# IO.net
KiCad netlist of a schematic drawn in Altium Designer
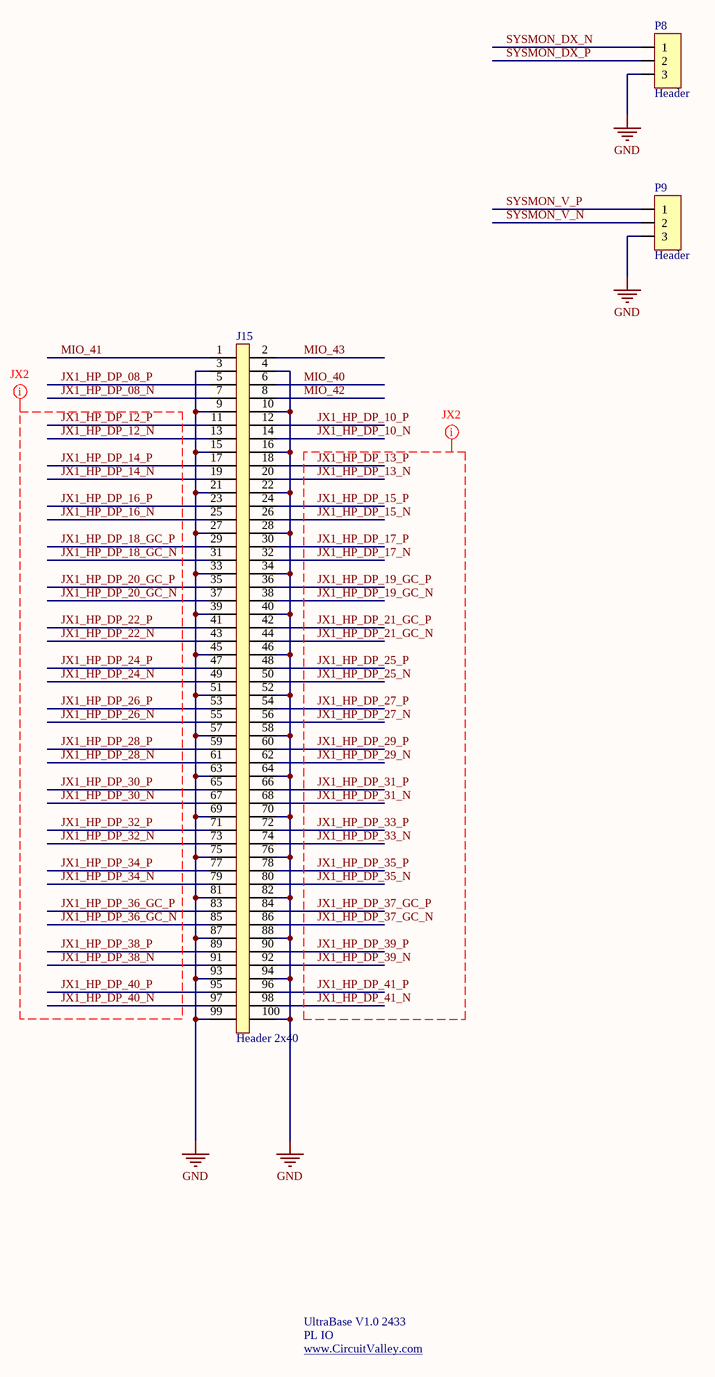
[diagram p0: IO.SchDoc]

(export (version "E")
  (design (tool "Eeschema 10.0.6"))
  (components
    (comp (ref "J15")
      (value "Header 2x40")
      (footprint "Header_2x50")
      (libsource (lib "cvlib") (part "Header_2x50"))
    )
    (comp (ref "P8")
      (value "Header")
      (footprint "Header3x")
      (description "3 Pin Header")
      (libsource (lib "cvlib") (part "Header_3Pin"))
    )
    (comp (ref "P9")
      (value "Header")
      (footprint "Header3x")
      (description "3 Pin Header")
      (libsource (lib "cvlib") (part "Header_3Pin"))
    )
  )
  (nets
    (net (code "1") (name "/JX1_HP_DP_08_N") (class "Default")
      (node (ref "J15") (pin "7") (pinfunction "7_7") (pintype "passive"))
    )
    (net (code "2") (name "/JX1_HP_DP_08_P") (class "Default")
      (node (ref "J15") (pin "5") (pinfunction "5_5") (pintype "passive"))
    )
    (net (code "3") (name "/JX1_HP_DP_10_N") (class "Default")
      (node (ref "J15") (pin "14") (pinfunction "14_14") (pintype "passive"))
    )
    (net (code "4") (name "/JX1_HP_DP_10_P") (class "Default")
      (node (ref "J15") (pin "12") (pinfunction "12_12") (pintype "passive"))
    )
    (net (code "5") (name "/JX1_HP_DP_12_N") (class "Default")
      (node (ref "J15") (pin "13") (pinfunction "13_13") (pintype "passive"))
    )
    (net (code "6") (name "/JX1_HP_DP_12_P") (class "Default")
      (node (ref "J15") (pin "11") (pinfunction "11_11") (pintype "passive"))
    )
    (net (code "7") (name "/JX1_HP_DP_13_N") (class "Default")
      (node (ref "J15") (pin "20") (pinfunction "20_20") (pintype "passive"))
    )
    (net (code "8") (name "/JX1_HP_DP_13_P") (class "Default")
      (node (ref "J15") (pin "18") (pinfunction "18_18") (pintype "passive"))
    )
    (net (code "9") (name "/JX1_HP_DP_14_N") (class "Default")
      (node (ref "J15") (pin "19") (pinfunction "19_19") (pintype "passive"))
    )
    (net (code "10") (name "/JX1_HP_DP_14_P") (class "Default")
      (node (ref "J15") (pin "17") (pinfunction "17_17") (pintype "passive"))
    )
    (net (code "11") (name "/JX1_HP_DP_15_N") (class "Default")
      (node (ref "J15") (pin "26") (pinfunction "26_26") (pintype "passive"))
    )
    (net (code "12") (name "/JX1_HP_DP_15_P") (class "Default")
      (node (ref "J15") (pin "24") (pinfunction "24_24") (pintype "passive"))
    )
    (net (code "13") (name "/JX1_HP_DP_16_N") (class "Default")
      (node (ref "J15") (pin "25") (pinfunction "25_25") (pintype "passive"))
    )
    (net (code "14") (name "/JX1_HP_DP_16_P") (class "Default")
      (node (ref "J15") (pin "23") (pinfunction "23_23") (pintype "passive"))
    )
    (net (code "15") (name "/JX1_HP_DP_17_N") (class "Default")
      (node (ref "J15") (pin "32") (pinfunction "32_32") (pintype "passive"))
    )
    (net (code "16") (name "/JX1_HP_DP_17_P") (class "Default")
      (node (ref "J15") (pin "30") (pinfunction "30_30") (pintype "passive"))
    )
    (net (code "17") (name "/JX1_HP_DP_18_GC_N") (class "Default")
      (node (ref "J15") (pin "31") (pinfunction "31_31") (pintype "passive"))
    )
    (net (code "18") (name "/JX1_HP_DP_18_GC_P") (class "Default")
      (node (ref "J15") (pin "29") (pinfunction "29_29") (pintype "passive"))
    )
    (net (code "19") (name "/JX1_HP_DP_19_GC_N") (class "Default")
      (node (ref "J15") (pin "38") (pinfunction "38_38") (pintype "passive"))
    )
    (net (code "20") (name "/JX1_HP_DP_19_GC_P") (class "Default")
      (node (ref "J15") (pin "36") (pinfunction "36_36") (pintype "passive"))
    )
    (net (code "21") (name "/JX1_HP_DP_20_GC_N") (class "Default")
      (node (ref "J15") (pin "37") (pinfunction "37_37") (pintype "passive"))
    )
    (net (code "22") (name "/JX1_HP_DP_20_GC_P") (class "Default")
      (node (ref "J15") (pin "35") (pinfunction "35_35") (pintype "passive"))
    )
    (net (code "23") (name "/JX1_HP_DP_21_GC_N") (class "Default")
      (node (ref "J15") (pin "44") (pinfunction "44_44") (pintype "passive"))
    )
    (net (code "24") (name "/JX1_HP_DP_21_GC_P") (class "Default")
      (node (ref "J15") (pin "42") (pinfunction "42_42") (pintype "passive"))
    )
    (net (code "25") (name "/JX1_HP_DP_22_N") (class "Default")
      (node (ref "J15") (pin "43") (pinfunction "43_43") (pintype "passive"))
    )
    (net (code "26") (name "/JX1_HP_DP_22_P") (class "Default")
      (node (ref "J15") (pin "41") (pinfunction "41_41") (pintype "passive"))
    )
    (net (code "27") (name "/JX1_HP_DP_24_N") (class "Default")
      (node (ref "J15") (pin "49") (pinfunction "49_49") (pintype "passive"))
    )
    (net (code "28") (name "/JX1_HP_DP_24_P") (class "Default")
      (node (ref "J15") (pin "47") (pinfunction "47_47") (pintype "passive"))
    )
    (net (code "29") (name "/JX1_HP_DP_25_N") (class "Default")
      (node (ref "J15") (pin "50") (pinfunction "50_50") (pintype "passive"))
    )
    (net (code "30") (name "/JX1_HP_DP_25_P") (class "Default")
      (node (ref "J15") (pin "48") (pinfunction "48_48") (pintype "passive"))
    )
    (net (code "31") (name "/JX1_HP_DP_26_N") (class "Default")
      (node (ref "J15") (pin "55") (pinfunction "55_55") (pintype "passive"))
    )
    (net (code "32") (name "/JX1_HP_DP_26_P") (class "Default")
      (node (ref "J15") (pin "53") (pinfunction "53_53") (pintype "passive"))
    )
    (net (code "33") (name "/JX1_HP_DP_27_N") (class "Default")
      (node (ref "J15") (pin "56") (pinfunction "56_56") (pintype "passive"))
    )
    (net (code "34") (name "/JX1_HP_DP_27_P") (class "Default")
      (node (ref "J15") (pin "54") (pinfunction "54_54") (pintype "passive"))
    )
    (net (code "35") (name "/JX1_HP_DP_28_N") (class "Default")
      (node (ref "J15") (pin "61") (pinfunction "61_61") (pintype "passive"))
    )
    (net (code "36") (name "/JX1_HP_DP_28_P") (class "Default")
      (node (ref "J15") (pin "59") (pinfunction "59_59") (pintype "passive"))
    )
    (net (code "37") (name "/JX1_HP_DP_29_N") (class "Default")
      (node (ref "J15") (pin "62") (pinfunction "62_62") (pintype "passive"))
    )
    (net (code "38") (name "/JX1_HP_DP_29_P") (class "Default")
      (node (ref "J15") (pin "60") (pinfunction "60_60") (pintype "passive"))
    )
    (net (code "39") (name "/JX1_HP_DP_30_N") (class "Default")
      (node (ref "J15") (pin "67") (pinfunction "67_67") (pintype "passive"))
    )
    (net (code "40") (name "/JX1_HP_DP_30_P") (class "Default")
      (node (ref "J15") (pin "65") (pinfunction "65_65") (pintype "passive"))
    )
    (net (code "41") (name "/JX1_HP_DP_31_N") (class "Default")
      (node (ref "J15") (pin "68") (pinfunction "68_68") (pintype "passive"))
    )
    (net (code "42") (name "/JX1_HP_DP_31_P") (class "Default")
      (node (ref "J15") (pin "66") (pinfunction "66_66") (pintype "passive"))
    )
    (net (code "43") (name "/JX1_HP_DP_32_N") (class "Default")
      (node (ref "J15") (pin "73") (pinfunction "73_73") (pintype "passive"))
    )
    (net (code "44") (name "/JX1_HP_DP_32_P") (class "Default")
      (node (ref "J15") (pin "71") (pinfunction "71_71") (pintype "passive"))
    )
    (net (code "45") (name "/JX1_HP_DP_33_N") (class "Default")
      (node (ref "J15") (pin "74") (pinfunction "74_74") (pintype "passive"))
    )
    (net (code "46") (name "/JX1_HP_DP_33_P") (class "Default")
      (node (ref "J15") (pin "72") (pinfunction "72_72") (pintype "passive"))
    )
    (net (code "47") (name "/JX1_HP_DP_34_N") (class "Default")
      (node (ref "J15") (pin "79") (pinfunction "79_79") (pintype "passive"))
    )
    (net (code "48") (name "/JX1_HP_DP_34_P") (class "Default")
      (node (ref "J15") (pin "77") (pinfunction "77_77") (pintype "passive"))
    )
    (net (code "49") (name "/JX1_HP_DP_35_N") (class "Default")
      (node (ref "J15") (pin "80") (pinfunction "80_80") (pintype "passive"))
    )
    (net (code "50") (name "/JX1_HP_DP_35_P") (class "Default")
      (node (ref "J15") (pin "78") (pinfunction "78_78") (pintype "passive"))
    )
    (net (code "51") (name "/JX1_HP_DP_36_GC_N") (class "Default")
      (node (ref "J15") (pin "85") (pinfunction "85_85") (pintype "passive"))
    )
    (net (code "52") (name "/JX1_HP_DP_36_GC_P") (class "Default")
      (node (ref "J15") (pin "83") (pinfunction "83_83") (pintype "passive"))
    )
    (net (code "53") (name "/JX1_HP_DP_37_GC_N") (class "Default")
      (node (ref "J15") (pin "86") (pinfunction "86_86") (pintype "passive"))
    )
    (net (code "54") (name "/JX1_HP_DP_37_GC_P") (class "Default")
      (node (ref "J15") (pin "84") (pinfunction "84_84") (pintype "passive"))
    )
    (net (code "55") (name "/JX1_HP_DP_38_N") (class "Default")
      (node (ref "J15") (pin "91") (pinfunction "91_91") (pintype "passive"))
    )
    (net (code "56") (name "/JX1_HP_DP_38_P") (class "Default")
      (node (ref "J15") (pin "89") (pinfunction "89_89") (pintype "passive"))
    )
    (net (code "57") (name "/JX1_HP_DP_39_N") (class "Default")
      (node (ref "J15") (pin "92") (pinfunction "92_92") (pintype "passive"))
    )
    (net (code "58") (name "/JX1_HP_DP_39_P") (class "Default")
      (node (ref "J15") (pin "90") (pinfunction "90_90") (pintype "passive"))
    )
    (net (code "59") (name "/JX1_HP_DP_40_N") (class "Default")
      (node (ref "J15") (pin "97") (pinfunction "97_97") (pintype "passive"))
    )
    (net (code "60") (name "/JX1_HP_DP_40_P") (class "Default")
      (node (ref "J15") (pin "95") (pinfunction "95_95") (pintype "passive"))
    )
    (net (code "61") (name "/JX1_HP_DP_41_N") (class "Default")
      (node (ref "J15") (pin "98") (pinfunction "98_98") (pintype "passive"))
    )
    (net (code "62") (name "/JX1_HP_DP_41_P") (class "Default")
      (node (ref "J15") (pin "96") (pinfunction "96_96") (pintype "passive"))
    )
    (net (code "63") (name "/MIO_40") (class "Default")
      (node (ref "J15") (pin "6") (pinfunction "6_6") (pintype "passive"))
    )
    (net (code "64") (name "/MIO_41") (class "Default")
      (node (ref "J15") (pin "1") (pinfunction "1_1") (pintype "passive"))
    )
    (net (code "65") (name "/MIO_42") (class "Default")
      (node (ref "J15") (pin "8") (pinfunction "8_8") (pintype "passive"))
    )
    (net (code "66") (name "/MIO_43") (class "Default")
      (node (ref "J15") (pin "2") (pinfunction "2_2") (pintype "passive"))
    )
    (net (code "67") (name "/SYSMON_DX_N") (class "Default")
      (node (ref "P8") (pin "1") (pinfunction "1_1") (pintype "passive"))
    )
    (net (code "68") (name "/SYSMON_DX_P") (class "Default")
      (node (ref "P8") (pin "2") (pinfunction "2_2") (pintype "passive"))
    )
    (net (code "69") (name "/SYSMON_V_N") (class "Default")
      (node (ref "P9") (pin "2") (pinfunction "2_2") (pintype "passive"))
    )
    (net (code "70") (name "/SYSMON_V_P") (class "Default")
      (node (ref "P9") (pin "1") (pinfunction "1_1") (pintype "passive"))
    )
    (net (code "71") (name "GND") (class "Default")
      (node (ref "J15") (pin "10") (pinfunction "10_10") (pintype "passive"))
      (node (ref "J15") (pin "100") (pinfunction "100_100") (pintype "passive"))
      (node (ref "J15") (pin "15") (pinfunction "15_15") (pintype "passive"))
      (node (ref "J15") (pin "16") (pinfunction "16_16") (pintype "passive"))
      (node (ref "J15") (pin "21") (pinfunction "21_21") (pintype "passive"))
      (node (ref "J15") (pin "22") (pinfunction "22_22") (pintype "passive"))
      (node (ref "J15") (pin "27") (pinfunction "27_27") (pintype "passive"))
      (node (ref "J15") (pin "28") (pinfunction "28_28") (pintype "passive"))
      (node (ref "J15") (pin "3") (pinfunction "3_3") (pintype "passive"))
      (node (ref "J15") (pin "33") (pinfunction "33_33") (pintype "passive"))
      (node (ref "J15") (pin "34") (pinfunction "34_34") (pintype "passive"))
      (node (ref "J15") (pin "39") (pinfunction "39_39") (pintype "passive"))
      (node (ref "J15") (pin "4") (pinfunction "4_4") (pintype "passive"))
      (node (ref "J15") (pin "40") (pinfunction "40_40") (pintype "passive"))
      (node (ref "J15") (pin "45") (pinfunction "45_45") (pintype "passive"))
      (node (ref "J15") (pin "46") (pinfunction "46_46") (pintype "passive"))
      (node (ref "J15") (pin "51") (pinfunction "51_51") (pintype "passive"))
      (node (ref "J15") (pin "52") (pinfunction "52_52") (pintype "passive"))
      (node (ref "J15") (pin "57") (pinfunction "57_57") (pintype "passive"))
      (node (ref "J15") (pin "58") (pinfunction "58_58") (pintype "passive"))
      (node (ref "J15") (pin "63") (pinfunction "63_63") (pintype "passive"))
      (node (ref "J15") (pin "64") (pinfunction "64_64") (pintype "passive"))
      (node (ref "J15") (pin "69") (pinfunction "69_69") (pintype "passive"))
      (node (ref "J15") (pin "70") (pinfunction "70_70") (pintype "passive"))
      (node (ref "J15") (pin "75") (pinfunction "75_75") (pintype "passive"))
      (node (ref "J15") (pin "76") (pinfunction "76_76") (pintype "passive"))
      (node (ref "J15") (pin "81") (pinfunction "81_81") (pintype "passive"))
      (node (ref "J15") (pin "82") (pinfunction "82_82") (pintype "passive"))
      (node (ref "J15") (pin "87") (pinfunction "87_87") (pintype "passive"))
      (node (ref "J15") (pin "88") (pinfunction "88_88") (pintype "passive"))
      (node (ref "J15") (pin "9") (pinfunction "9_9") (pintype "passive"))
      (node (ref "J15") (pin "93") (pinfunction "93_93") (pintype "passive"))
      (node (ref "J15") (pin "94") (pinfunction "94_94") (pintype "passive"))
      (node (ref "J15") (pin "99") (pinfunction "99_99") (pintype "passive"))
      (node (ref "P8") (pin "3") (pinfunction "3_3") (pintype "passive"))
      (node (ref "P9") (pin "3") (pinfunction "3_3") (pintype "passive"))
    )
  )
)
